# PDB_schem.net
KiCad netlist of a schematic drawn in Altium Designer
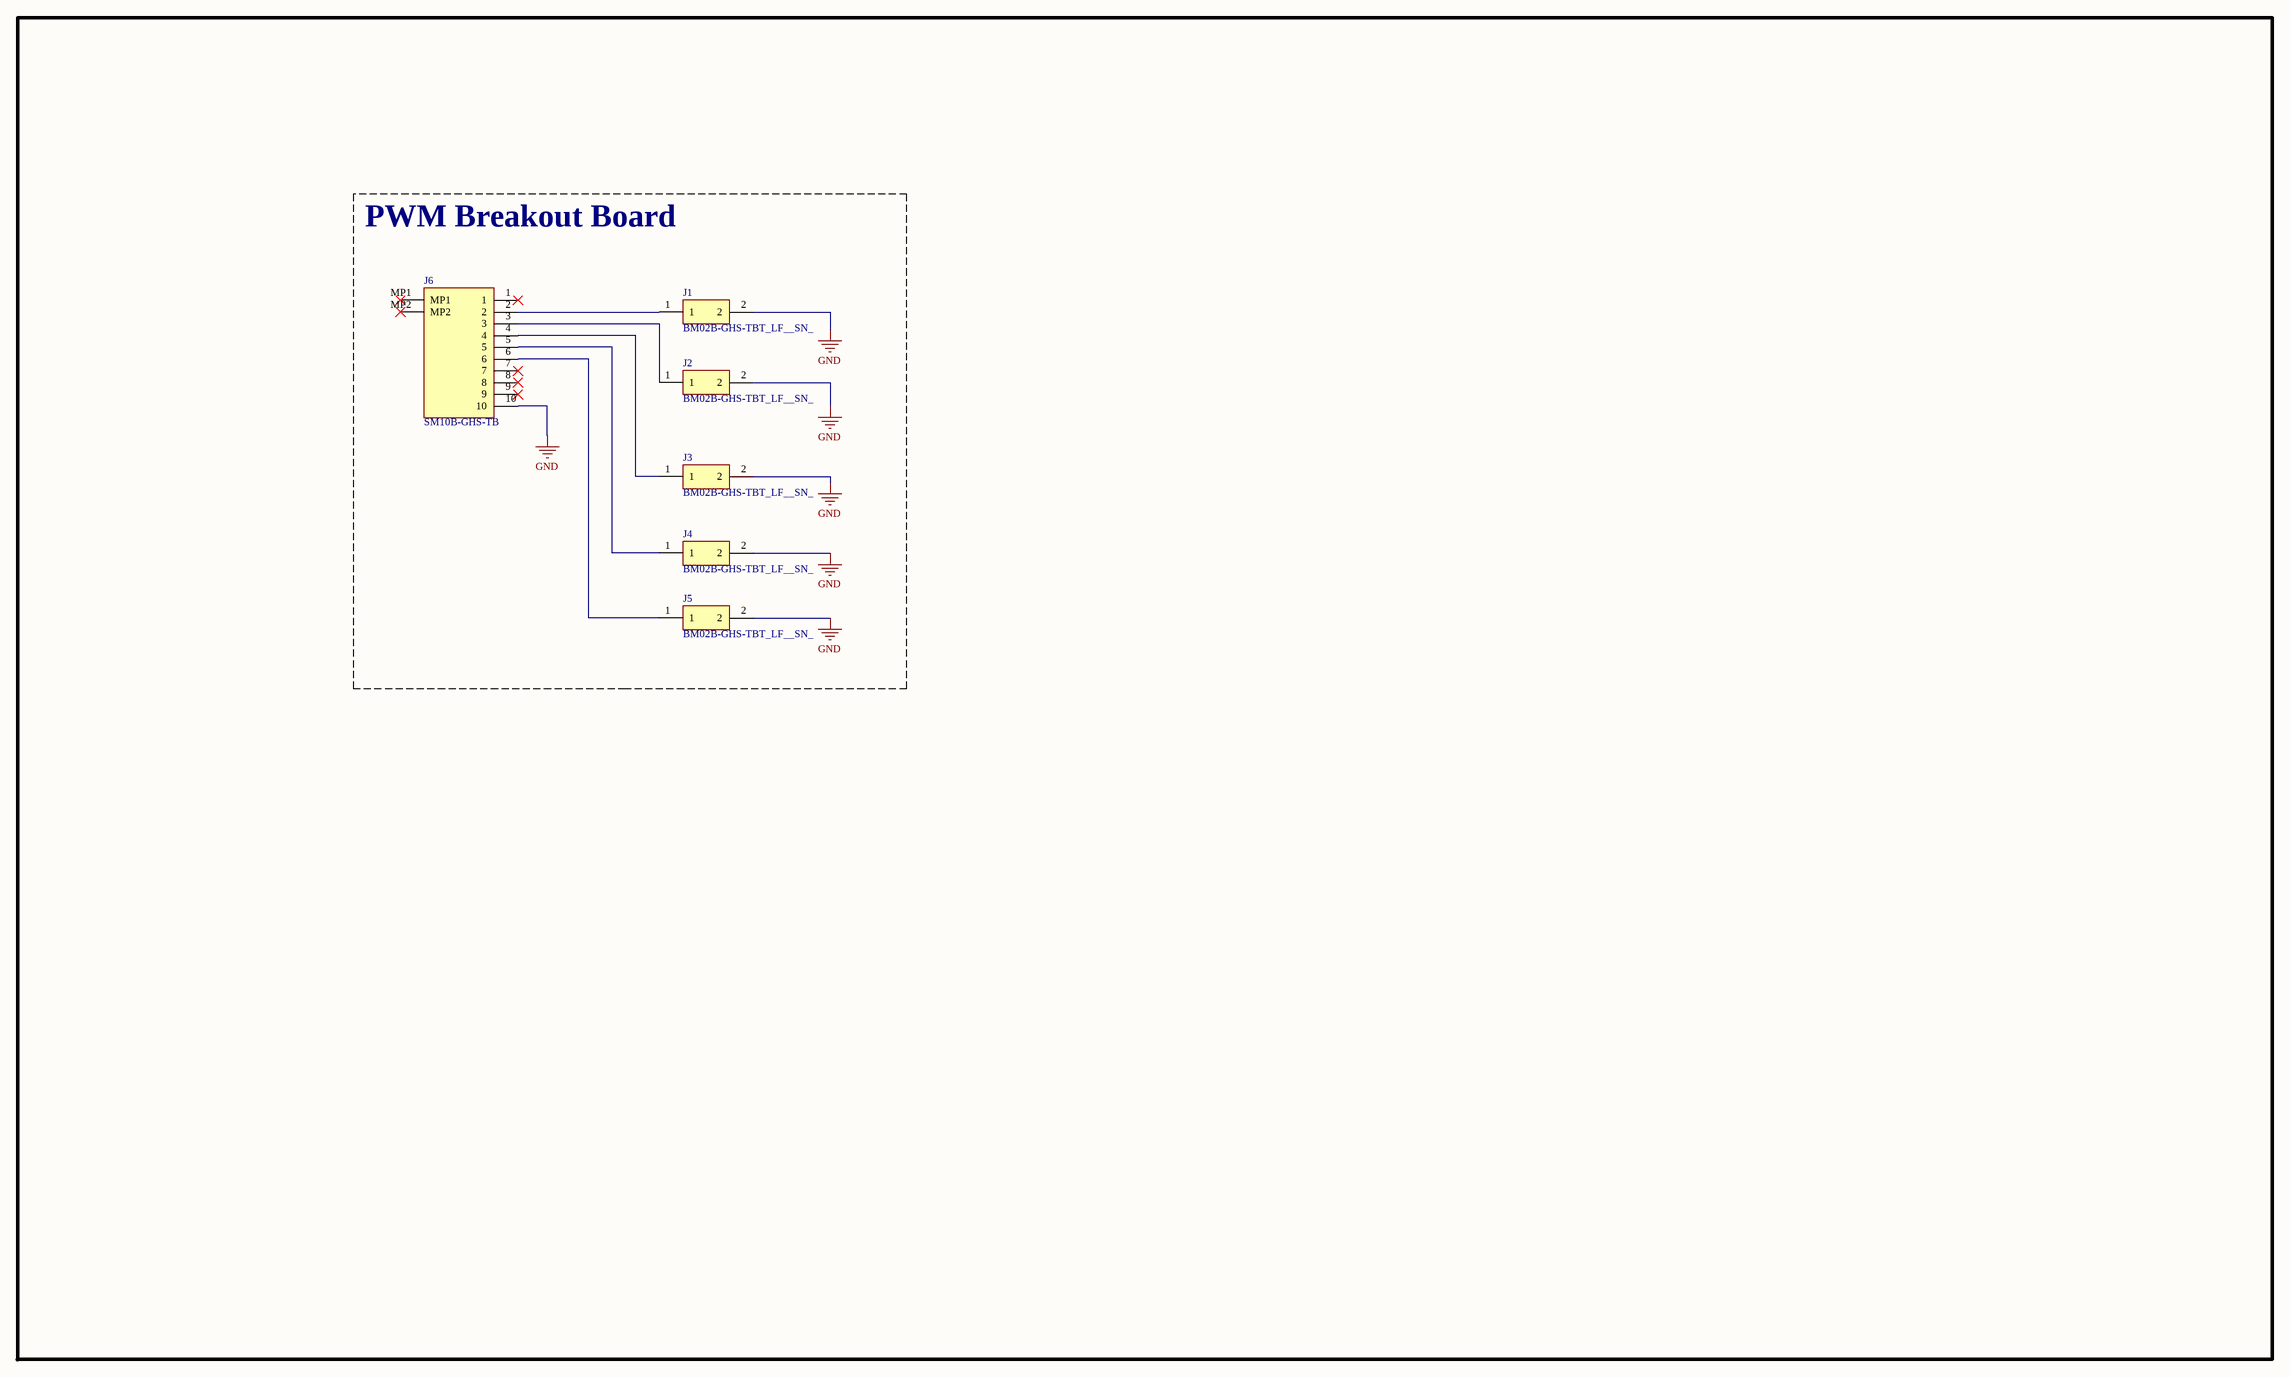
[diagram p0: PDB_schem.SchDoc]

(export (version "E")
  (design (tool "Eeschema 10.0.6"))
  (components
    (comp (ref "J1")
      (value "BM02B-GHS-TBT_LF__SN_")
      (footprint "BM02B-GHS-TBT_1")
      (description "Connector")
      (fields (field (name "MANUFACTURER_PART_NUMBER") "BM02B-GHS-TBT(LF)(SN)(N)"))
      (libsource (lib "Symbol_library") (part "BM02B-GHS-TBT_LF__SN__N_"))
    )
    (comp (ref "J2")
      (value "BM02B-GHS-TBT_LF__SN_")
      (footprint "BM02B-GHS-TBT_1")
      (description "Connector")
      (fields (field (name "MANUFACTURER_PART_NUMBER") "BM02B-GHS-TBT(LF)(SN)(N)"))
      (libsource (lib "Symbol_library") (part "BM02B-GHS-TBT_LF__SN__N_"))
    )
    (comp (ref "J3")
      (value "BM02B-GHS-TBT_LF__SN_")
      (footprint "BM02B-GHS-TBT_1")
      (description "Connector")
      (fields (field (name "MANUFACTURER_PART_NUMBER") "BM02B-GHS-TBT(LF)(SN)(N)"))
      (libsource (lib "Symbol_library") (part "BM02B-GHS-TBT_LF__SN__N_"))
    )
    (comp (ref "J4")
      (value "BM02B-GHS-TBT_LF__SN_")
      (footprint "BM02B-GHS-TBT_1")
      (description "Connector")
      (fields (field (name "MANUFACTURER_PART_NUMBER") "BM02B-GHS-TBT(LF)(SN)(N)"))
      (libsource (lib "Symbol_library") (part "BM02B-GHS-TBT_LF__SN__N_"))
    )
    (comp (ref "J5")
      (value "BM02B-GHS-TBT_LF__SN_")
      (footprint "BM02B-GHS-TBT_1")
      (description "Connector")
      (fields (field (name "MANUFACTURER_PART_NUMBER") "BM02B-GHS-TBT(LF)(SN)(N)"))
      (libsource (lib "Symbol_library") (part "BM02B-GHS-TBT_LF__SN__N_"))
    )
    (comp (ref "J6")
      (value "SM10B-GHS-TB")
      (footprint "SamacSys:SM10BGHSTB")
      (description "Connector")
      (libsource (lib "*") (part "SM10B-GHS-TB"))
    )
  )
  (nets
    (net (code "1") (name "GND") (class "Default")
      (node (ref "J1") (pin "2") (pinfunction "2_2") (pintype "passive"))
      (node (ref "J2") (pin "2") (pinfunction "2_2") (pintype "passive"))
      (node (ref "J3") (pin "2") (pinfunction "2_2") (pintype "passive"))
      (node (ref "J4") (pin "2") (pinfunction "2_2") (pintype "passive"))
      (node (ref "J5") (pin "2") (pinfunction "2_2") (pintype "passive"))
      (node (ref "J6") (pin "10") (pinfunction "10_10") (pintype "passive"))
    )
    (net (code "2") (name "Net-(J1-Pad1)") (class "Default")
      (node (ref "J1") (pin "1") (pinfunction "1_1") (pintype "passive"))
      (node (ref "J6") (pin "2") (pinfunction "2_2") (pintype "passive"))
    )
    (net (code "3") (name "Net-(J2-Pad1)") (class "Default")
      (node (ref "J2") (pin "1") (pinfunction "1_1") (pintype "passive"))
      (node (ref "J6") (pin "3") (pinfunction "3_3") (pintype "passive"))
    )
    (net (code "4") (name "Net-(J3-Pad1)") (class "Default")
      (node (ref "J3") (pin "1") (pinfunction "1_1") (pintype "passive"))
      (node (ref "J6") (pin "4") (pinfunction "4_4") (pintype "passive"))
    )
    (net (code "5") (name "Net-(J4-Pad1)") (class "Default")
      (node (ref "J4") (pin "1") (pinfunction "1_1") (pintype "passive"))
      (node (ref "J6") (pin "5") (pinfunction "5_5") (pintype "passive"))
    )
    (net (code "6") (name "Net-(J5-Pad1)") (class "Default")
      (node (ref "J5") (pin "1") (pinfunction "1_1") (pintype "passive"))
      (node (ref "J6") (pin "6") (pinfunction "6_6") (pintype "passive"))
    )
    (net (code "7") (name "unconnected-(J6-Pad1)") (class "Default")
      (node (ref "J6") (pin "1") (pinfunction "1_1") (pintype "passive+no_connect"))
    )
    (net (code "8") (name "unconnected-(J6-Pad7)") (class "Default")
      (node (ref "J6") (pin "7") (pinfunction "7_7") (pintype "passive+no_connect"))
    )
    (net (code "9") (name "unconnected-(J6-Pad8)") (class "Default")
      (node (ref "J6") (pin "8") (pinfunction "8_8") (pintype "passive+no_connect"))
    )
    (net (code "10") (name "unconnected-(J6-Pad9)") (class "Default")
      (node (ref "J6") (pin "9") (pinfunction "9_9") (pintype "passive+no_connect"))
    )
    (net (code "11") (name "unconnected-(J6-PadMP1)") (class "Default")
      (node (ref "J6") (pin "MP1") (pinfunction "MP1_MP1") (pintype "passive+no_connect"))
    )
    (net (code "12") (name "unconnected-(J6-PadMP2)") (class "Default")
      (node (ref "J6") (pin "MP2") (pinfunction "MP2_MP2") (pintype "passive+no_connect"))
    )
  )
)
